# ENR153_control_board.net
KiCad netlist of a schematic drawn in EAGLE
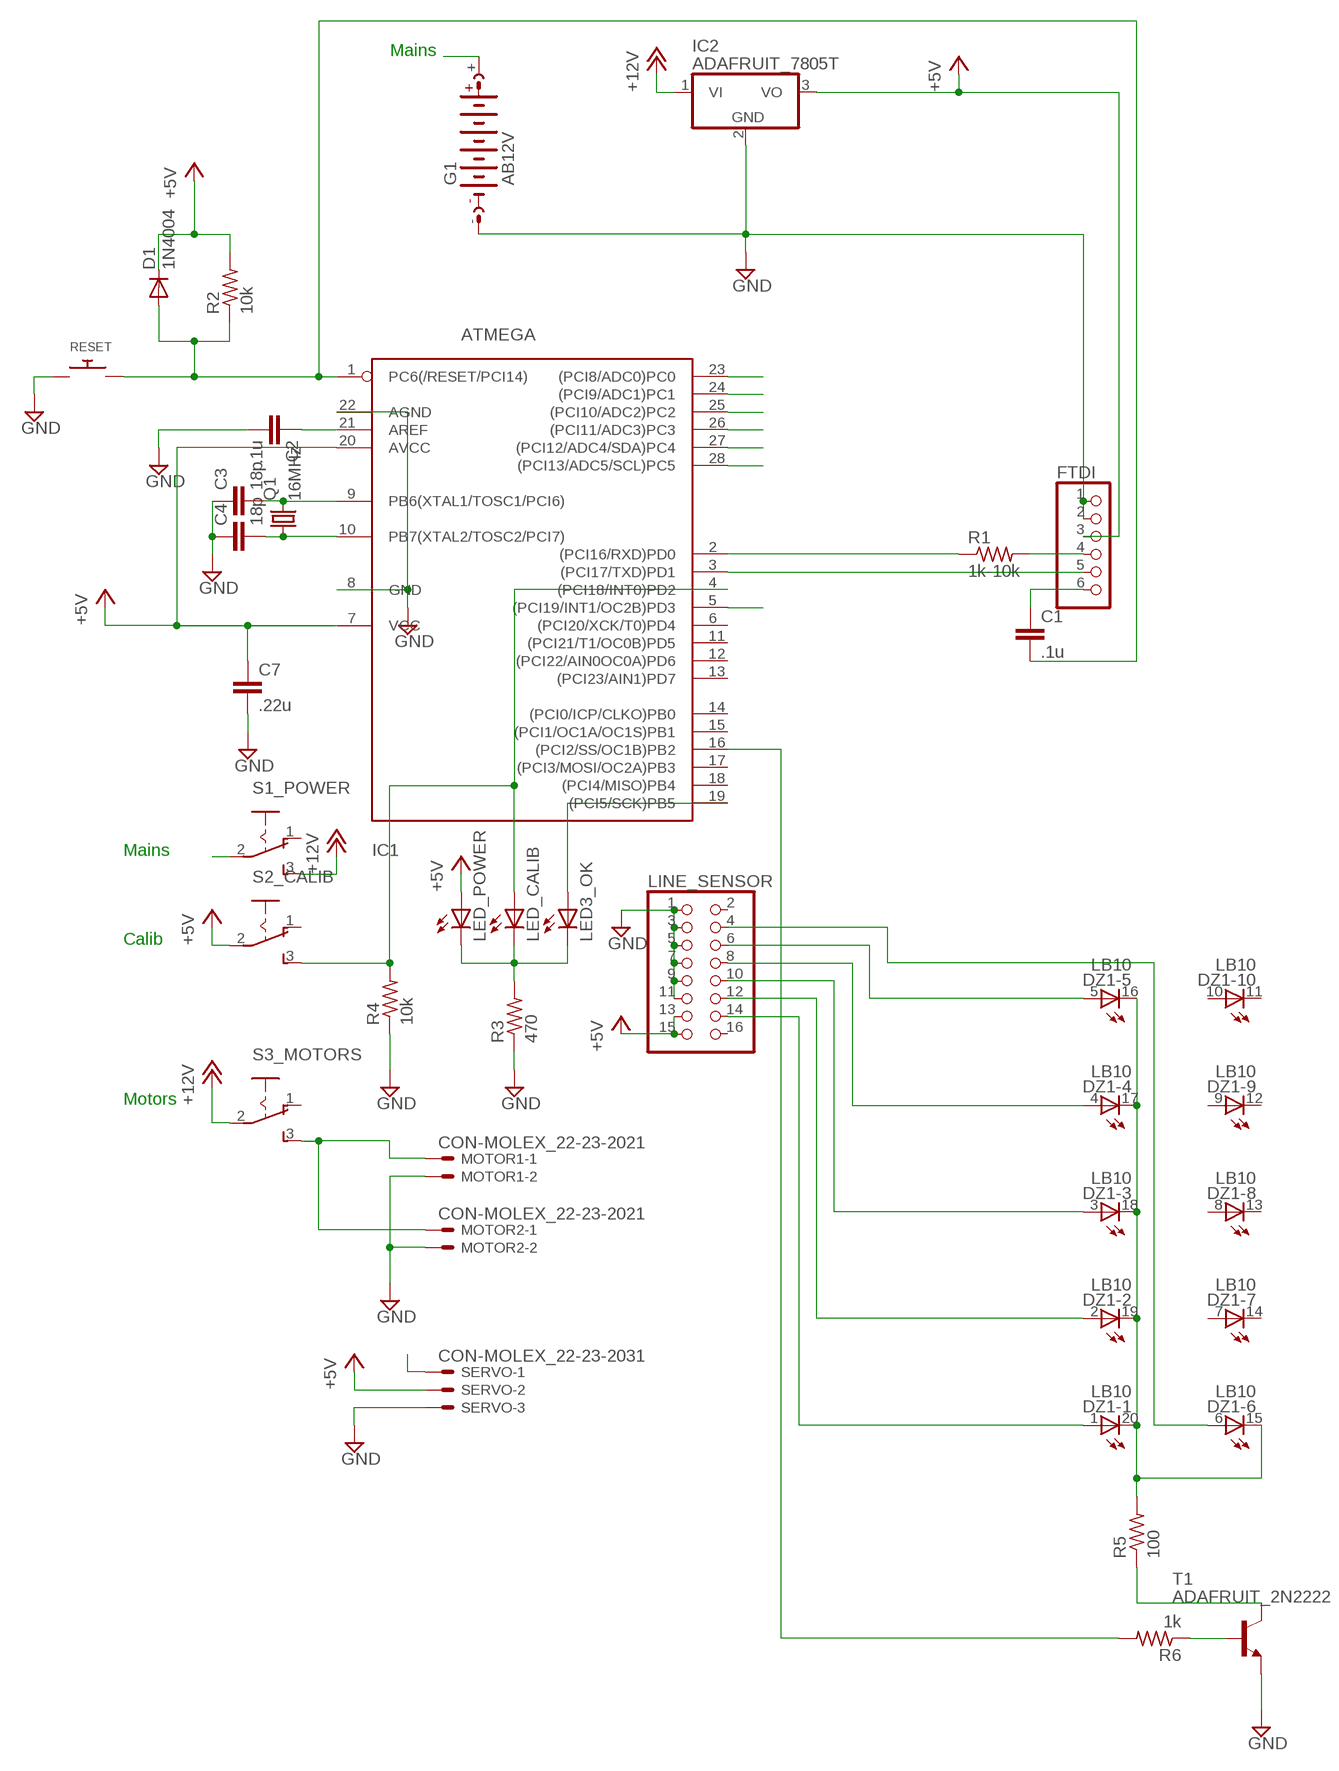
[diagram p0: schematic, sheet 1]

(export (version "E")
  (design (tool "Eeschema 10.0.6"))
  (components
    (comp (ref "C1")
      (value ".1u")
      (footprint "eagle-import:CAPACITOR-WIMA_C5B3")
      (libsource (lib "eagle-import") (part "CAPACITOR-WIMA_C5/3"))
    )
    (comp (ref "C2")
      (value ".1u")
      (footprint "eagle-import:CAPACITOR-WIMA_C5B3")
      (libsource (lib "eagle-import") (part "CAPACITOR-WIMA_C5/3"))
    )
    (comp (ref "C3")
      (value "18p")
      (footprint "eagle-import:CAPACITOR-WIMA_C5B3")
      (libsource (lib "eagle-import") (part "CAPACITOR-WIMA_C5/3"))
    )
    (comp (ref "C4")
      (value "18p")
      (footprint "eagle-import:CAPACITOR-WIMA_C5B3")
      (libsource (lib "eagle-import") (part "CAPACITOR-WIMA_C5/3"))
    )
    (comp (ref "C7")
      (value ".22u")
      (footprint "eagle-import:CAPACITOR-WIMA_C5B3")
      (libsource (lib "eagle-import") (part "CAPACITOR-WIMA_C5/3"))
    )
    (comp (ref "D1")
      (value "1N4004")
      (footprint "eagle-import:DIODE_DO35-7")
      (libsource (lib "eagle-import") (part "DIODE_1N4148DO35-7"))
    )
    (comp (ref "DZ1")
      (value "LB10")
      (footprint "eagle-import:LB10")
      (libsource (lib "eagle-import") (part "LB10"))
    )
    (comp (ref "FTDI")
      (value "PINHD-1X6")
      (footprint "eagle-import:1X06")
      (libsource (lib "eagle-import") (part "PINHD-1X6"))
    )
    (comp (ref "G1")
      (value "AB12V")
      (footprint "eagle-import:BATTERY_AB9V")
      (libsource (lib "eagle-import") (part "BATTERY_AB9V"))
    )
    (comp (ref "IC1")
      (value "ATMEGA")
      (footprint "eagle-import:DIL28-3")
      (libsource (lib "eagle-import") (part "ATMEGA168PV-10"))
    )
    (comp (ref "IC2")
      (value "ADAFRUIT_7805T")
      (footprint "eagle-import:ADAFRUIT_TO220H")
      (libsource (lib "eagle-import") (part "ADAFRUIT_78T05"))
    )
    (comp (ref "LED3_OK")
      (value "ADAFRUIT_LEDSQR2X5")
      (footprint "eagle-import:ADAFRUIT_LED2X5")
      (libsource (lib "eagle-import") (part "ADAFRUIT_LEDSQR2X5"))
    )
    (comp (ref "LED_CALIB")
      (value "ADAFRUIT_LEDSQR2X5")
      (footprint "eagle-import:ADAFRUIT_LED2X5")
      (libsource (lib "eagle-import") (part "ADAFRUIT_LEDSQR2X5"))
    )
    (comp (ref "LED_POWER")
      (value "ADAFRUIT_LEDSQR2X5")
      (footprint "eagle-import:ADAFRUIT_LED2X5")
      (libsource (lib "eagle-import") (part "ADAFRUIT_LEDSQR2X5"))
    )
    (comp (ref "LINE_SENSOR")
      (value "PINHEAD_PINHD-2X8")
      (footprint "eagle-import:PINHEAD_2X08")
      (libsource (lib "eagle-import") (part "PINHEAD_PINHD-2X8"))
    )
    (comp (ref "MOTOR1")
      (value "CON-MOLEX_22-23-2021")
      (footprint "eagle-import:CON-MOLEX_22-23-2021")
      (fields (field (name "MF") "MOLEX") (field (name "MPN") "22-23-2021"))
      (libsource (lib "eagle-import") (part "CON-MOLEX_22-23-2021"))
    )
    (comp (ref "MOTOR2")
      (value "CON-MOLEX_22-23-2021")
      (footprint "eagle-import:CON-MOLEX_22-23-2021")
      (fields (field (name "MF") "MOLEX") (field (name "MPN") "22-23-2021"))
      (libsource (lib "eagle-import") (part "CON-MOLEX_22-23-2021"))
    )
    (comp (ref "Q1")
      (value "16MHz")
      (footprint "eagle-import:ADAFRUIT_HC49_S")
      (libsource (lib "eagle-import") (part "ADAFRUIT_CRYSTALHC49S"))
    )
    (comp (ref "R1")
      (value "1k-10k")
      (footprint "eagle-import:ADAFRUIT_0207_7")
      (libsource (lib "eagle-import") (part "ADAFRUIT_R-US_0207/7"))
    )
    (comp (ref "R2")
      (value "10k")
      (footprint "eagle-import:ADAFRUIT_0207_7")
      (libsource (lib "eagle-import") (part "ADAFRUIT_R-US_0207/7"))
    )
    (comp (ref "R3")
      (value "470")
      (footprint "eagle-import:ADAFRUIT_0207_7")
      (libsource (lib "eagle-import") (part "ADAFRUIT_R-US_0207/7"))
    )
    (comp (ref "R4")
      (value "10k")
      (footprint "eagle-import:ADAFRUIT_0207_7")
      (libsource (lib "eagle-import") (part "ADAFRUIT_R-US_0207/7"))
    )
    (comp (ref "R5")
      (value "100")
      (footprint "eagle-import:ADAFRUIT_0207_7")
      (libsource (lib "eagle-import") (part "ADAFRUIT_R-US_0207/7"))
    )
    (comp (ref "R6")
      (value "1k")
      (footprint "eagle-import:ADAFRUIT_0207_7")
      (libsource (lib "eagle-import") (part "ADAFRUIT_R-US_0207/7"))
    )
    (comp (ref "RESET")
      (value "ADAFRUIT_SWITCH_PUSHBUTTONEVQ-PE")
      (footprint "eagle-import:ADAFRUIT_TACT_PANA-EVQ")
      (libsource (lib "eagle-import") (part "ADAFRUIT_SWITCH_PUSHBUTTONEVQ-PE"))
    )
    (comp (ref "S1_POWER")
      (value "SWITCH_255SB")
      (footprint "eagle-import:SWITCH_255SB")
      (libsource (lib "eagle-import") (part "SWITCH_255SB"))
    )
    (comp (ref "S2_CALIB")
      (value "SWITCH_255SB")
      (footprint "eagle-import:SWITCH_255SB")
      (libsource (lib "eagle-import") (part "SWITCH_255SB"))
    )
    (comp (ref "S3_MOTORS")
      (value "SWITCH_255SB")
      (footprint "eagle-import:SWITCH_255SB")
      (libsource (lib "eagle-import") (part "SWITCH_255SB"))
    )
    (comp (ref "SERVO")
      (value "CON-MOLEX_22-23-2031")
      (footprint "eagle-import:CON-MOLEX_22-23-2031")
      (fields (field (name "MF") "MOLEX") (field (name "MPN") "22-23-2031"))
      (libsource (lib "eagle-import") (part "CON-MOLEX_22-23-2031"))
    )
    (comp (ref "T1")
      (value "ADAFRUIT_2N2222")
      (footprint "eagle-import:ADAFRUIT_TO92-EBC-OVAL")
      (libsource (lib "eagle-import") (part "ADAFRUIT_2N2222"))
    )
  )
  (nets
    (net (code "1") (name "+5V") (class "Default")
      (node (ref "C7") (pin "1") (pinfunction "1_1") (pintype "passive"))
      (node (ref "D1") (pin "C") (pinfunction "C_C") (pintype "passive"))
      (node (ref "FTDI") (pin "3") (pinfunction "3_3") (pintype "passive"))
      (node (ref "IC1") (pin "20") (pinfunction "AVCC_20") (pintype "bidirectional"))
      (node (ref "IC1") (pin "7") (pinfunction "VCC_7") (pintype "bidirectional"))
      (node (ref "IC2") (pin "3") (pinfunction "VO_3") (pintype "passive"))
      (node (ref "LED_POWER") (pin "A") (pinfunction "A_A") (pintype "passive"))
      (node (ref "LINE_SENSOR") (pin "13") (pinfunction "13_13") (pintype "passive"))
      (node (ref "LINE_SENSOR") (pin "15") (pinfunction "15_15") (pintype "passive"))
      (node (ref "R2") (pin "2") (pinfunction "2_2") (pintype "passive"))
      (node (ref "S2_CALIB") (pin "2") (pinfunction "P_2") (pintype "passive"))
      (node (ref "SERVO") (pin "2") (pinfunction "S_2") (pintype "passive"))
    )
    (net (code "2") (name "+12V") (class "Default")
      (node (ref "IC2") (pin "1") (pinfunction "VI_1") (pintype "input"))
      (node (ref "S1_POWER") (pin "3") (pinfunction "S_3") (pintype "passive"))
      (node (ref "S3_MOTORS") (pin "2") (pinfunction "P_2") (pintype "passive"))
    )
    (net (code "3") (name "/A0") (class "Default")
      (node (ref "DZ1") (pin "6") (pinfunction "A_6") (pintype "passive"))
      (node (ref "IC1") (pin "23") (pinfunction "(PCI8/ADC0)PC0_23") (pintype "bidirectional"))
      (node (ref "LINE_SENSOR") (pin "4") (pinfunction "4_4") (pintype "passive"))
    )
    (net (code "4") (name "/A1") (class "Default")
      (node (ref "DZ1") (pin "5") (pinfunction "A_5") (pintype "passive"))
      (node (ref "IC1") (pin "24") (pinfunction "(PCI9/ADC1)PC1_24") (pintype "bidirectional"))
      (node (ref "LINE_SENSOR") (pin "6") (pinfunction "6_6") (pintype "passive"))
    )
    (net (code "5") (name "/A2") (class "Default")
      (node (ref "DZ1") (pin "4") (pinfunction "A_4") (pintype "passive"))
      (node (ref "IC1") (pin "25") (pinfunction "(PCI10/ADC2)PC2_25") (pintype "bidirectional"))
      (node (ref "LINE_SENSOR") (pin "8") (pinfunction "8_8") (pintype "passive"))
    )
    (net (code "6") (name "/A3") (class "Default")
      (node (ref "DZ1") (pin "3") (pinfunction "A_3") (pintype "passive"))
      (node (ref "IC1") (pin "26") (pinfunction "(PCI11/ADC3)PC3_26") (pintype "bidirectional"))
      (node (ref "LINE_SENSOR") (pin "10") (pinfunction "10_10") (pintype "passive"))
    )
    (net (code "7") (name "/A4") (class "Default")
      (node (ref "DZ1") (pin "2") (pinfunction "A_2") (pintype "passive"))
      (node (ref "IC1") (pin "27") (pinfunction "(PCI12/ADC4/SDA)PC4_27") (pintype "bidirectional"))
      (node (ref "LINE_SENSOR") (pin "12") (pinfunction "12_12") (pintype "passive"))
    )
    (net (code "8") (name "/A5") (class "Default")
      (node (ref "DZ1") (pin "1") (pinfunction "A_1") (pintype "passive"))
      (node (ref "IC1") (pin "28") (pinfunction "(PCI13/ADC5/SCL)PC5_28") (pintype "bidirectional"))
      (node (ref "LINE_SENSOR") (pin "14") (pinfunction "14_14") (pintype "passive"))
    )
    (net (code "9") (name "/MAINS") (class "Default")
      (node (ref "G1") (pin "+") (pinfunction "+_+") (pintype "passive"))
      (node (ref "S1_POWER") (pin "2") (pinfunction "P_2") (pintype "passive"))
    )
    (net (code "10") (name "/SERVO") (class "Default")
      (node (ref "IC1") (pin "5") (pinfunction "(PCI19/INT1/OC2B)PD3_5") (pintype "bidirectional"))
      (node (ref "SERVO") (pin "1") (pinfunction "S_1") (pintype "passive"))
    )
    (net (code "11") (name "GND") (class "Default")
      (node (ref "C2") (pin "2") (pinfunction "2_2") (pintype "passive"))
      (node (ref "C3") (pin "1") (pinfunction "1_1") (pintype "passive"))
      (node (ref "C4") (pin "1") (pinfunction "1_1") (pintype "passive"))
      (node (ref "C7") (pin "2") (pinfunction "2_2") (pintype "passive"))
      (node (ref "FTDI") (pin "1") (pinfunction "1_1") (pintype "passive"))
      (node (ref "FTDI") (pin "2") (pinfunction "2_2") (pintype "passive"))
      (node (ref "G1") (pin "-") (pinfunction "-_-") (pintype "passive"))
      (node (ref "IC1") (pin "22") (pinfunction "AGND_22") (pintype "bidirectional"))
      (node (ref "IC1") (pin "8") (pinfunction "GND_8") (pintype "bidirectional"))
      (node (ref "IC2") (pin "2") (pinfunction "GND_2") (pintype "passive"))
      (node (ref "LINE_SENSOR") (pin "1") (pinfunction "1_1") (pintype "passive"))
      (node (ref "LINE_SENSOR") (pin "11") (pinfunction "11_11") (pintype "passive"))
      (node (ref "LINE_SENSOR") (pin "3") (pinfunction "3_3") (pintype "passive"))
      (node (ref "LINE_SENSOR") (pin "5") (pinfunction "5_5") (pintype "passive"))
      (node (ref "LINE_SENSOR") (pin "7") (pinfunction "7_7") (pintype "passive"))
      (node (ref "LINE_SENSOR") (pin "9") (pinfunction "9_9") (pintype "passive"))
      (node (ref "MOTOR1") (pin "2") (pinfunction "S_2") (pintype "passive"))
      (node (ref "MOTOR2") (pin "2") (pinfunction "S_2") (pintype "passive"))
      (node (ref "R3") (pin "1") (pinfunction "1_1") (pintype "passive"))
      (node (ref "R4") (pin "1") (pinfunction "1_1") (pintype "passive"))
      (node (ref "RESET") (pin "P$1") (pinfunction "P$1_P$1") (pintype "passive"))
      (node (ref "SERVO") (pin "3") (pinfunction "S_3") (pintype "passive"))
      (node (ref "T1") (pin "E") (pinfunction "E_E") (pintype "passive"))
    )
    (net (code "12") (name "Net-(C1-Pad1)") (class "Default")
      (node (ref "C1") (pin "1") (pinfunction "1_1") (pintype "passive"))
      (node (ref "FTDI") (pin "6") (pinfunction "6_6") (pintype "passive"))
    )
    (net (code "13") (name "Net-(DZ1A-C)") (class "Default")
      (node (ref "DZ1") (pin "15") (pinfunction "C_15") (pintype "passive"))
      (node (ref "DZ1") (pin "16") (pinfunction "C_16") (pintype "passive"))
      (node (ref "DZ1") (pin "17") (pinfunction "C_17") (pintype "passive"))
      (node (ref "DZ1") (pin "18") (pinfunction "C_18") (pintype "passive"))
      (node (ref "DZ1") (pin "19") (pinfunction "C_19") (pintype "passive"))
      (node (ref "DZ1") (pin "20") (pinfunction "C_20") (pintype "passive"))
      (node (ref "R5") (pin "2") (pinfunction "2_2") (pintype "passive"))
    )
    (net (code "14") (name "Net-(FTDI-Pad4)") (class "Default")
      (node (ref "FTDI") (pin "4") (pinfunction "4_4") (pintype "passive"))
      (node (ref "R1") (pin "2") (pinfunction "2_2") (pintype "passive"))
    )
    (net (code "15") (name "Net-(IC1-(PCI2{slash}SS{slash}OC1B)PB2)") (class "Default")
      (node (ref "IC1") (pin "16") (pinfunction "(PCI2/SS/OC1B)PB2_16") (pintype "bidirectional"))
      (node (ref "R6") (pin "2") (pinfunction "2_2") (pintype "passive"))
    )
    (net (code "16") (name "Net-(IC1-(PCI5{slash}SCK)PB5)") (class "Default")
      (node (ref "IC1") (pin "19") (pinfunction "(PCI5/SCK)PB5_19") (pintype "bidirectional"))
      (node (ref "LED3_OK") (pin "A") (pinfunction "A_A") (pintype "passive"))
    )
    (net (code "17") (name "Net-(IC1-(PCI16{slash}RXD)PD0)") (class "Default")
      (node (ref "IC1") (pin "2") (pinfunction "(PCI16/RXD)PD0_2") (pintype "bidirectional"))
      (node (ref "R1") (pin "1") (pinfunction "1_1") (pintype "passive"))
    )
    (net (code "18") (name "Net-(IC1-(PCI17{slash}TXD)PD1)") (class "Default")
      (node (ref "FTDI") (pin "5") (pinfunction "5_5") (pintype "passive"))
      (node (ref "IC1") (pin "3") (pinfunction "(PCI17/TXD)PD1_3") (pintype "bidirectional"))
    )
    (net (code "19") (name "Net-(IC1-(PCI18{slash}INT0)PD2)") (class "Default")
      (node (ref "IC1") (pin "4") (pinfunction "(PCI18/INT0)PD2_4") (pintype "bidirectional"))
      (node (ref "LED_CALIB") (pin "A") (pinfunction "A_A") (pintype "passive"))
      (node (ref "R4") (pin "2") (pinfunction "2_2") (pintype "passive"))
      (node (ref "S2_CALIB") (pin "3") (pinfunction "S_3") (pintype "passive"))
    )
    (net (code "20") (name "Net-(IC1-AREF)") (class "Default")
      (node (ref "C2") (pin "1") (pinfunction "1_1") (pintype "passive"))
      (node (ref "IC1") (pin "21") (pinfunction "AREF_21") (pintype "bidirectional"))
    )
    (net (code "21") (name "Net-(IC1-PB6(XTAL1{slash}TOSC1{slash}PCI6))") (class "Default")
      (node (ref "C3") (pin "2") (pinfunction "2_2") (pintype "passive"))
      (node (ref "IC1") (pin "9") (pinfunction "PB6(XTAL1/TOSC1/PCI6)_9") (pintype "bidirectional"))
      (node (ref "Q1") (pin "2") (pinfunction "2_2") (pintype "passive"))
    )
    (net (code "22") (name "Net-(IC1-PB7(XTAL2{slash}TOSC2{slash}PCI7))") (class "Default")
      (node (ref "C4") (pin "2") (pinfunction "2_2") (pintype "passive"))
      (node (ref "IC1") (pin "10") (pinfunction "PB7(XTAL2/TOSC2/PCI7)_10") (pintype "bidirectional"))
      (node (ref "Q1") (pin "1") (pinfunction "1_1") (pintype "passive"))
    )
    (net (code "23") (name "Net-(IC1-PC6({slash}RESET{slash}PCI14))") (class "Default")
      (node (ref "C1") (pin "2") (pinfunction "2_2") (pintype "passive"))
      (node (ref "D1") (pin "A") (pinfunction "A_A") (pintype "passive"))
      (node (ref "IC1") (pin "1") (pinfunction "PC6(/RESET/PCI14)_1") (pintype "bidirectional"))
      (node (ref "R2") (pin "1") (pinfunction "1_1") (pintype "passive"))
      (node (ref "RESET") (pin "P$2") (pinfunction "P$2_P$2") (pintype "passive"))
    )
    (net (code "24") (name "Net-(LED3_OK-C)") (class "Default")
      (node (ref "LED3_OK") (pin "K") (pinfunction "C_K") (pintype "passive"))
      (node (ref "LED_CALIB") (pin "K") (pinfunction "C_K") (pintype "passive"))
      (node (ref "LED_POWER") (pin "K") (pinfunction "C_K") (pintype "passive"))
      (node (ref "R3") (pin "2") (pinfunction "2_2") (pintype "passive"))
    )
    (net (code "25") (name "Net-(MOTOR1A-S)") (class "Default")
      (node (ref "MOTOR1") (pin "1") (pinfunction "S_1") (pintype "passive"))
      (node (ref "MOTOR2") (pin "1") (pinfunction "S_1") (pintype "passive"))
      (node (ref "S3_MOTORS") (pin "3") (pinfunction "S_3") (pintype "passive"))
    )
    (net (code "26") (name "Net-(R5-Pad1)") (class "Default")
      (node (ref "R5") (pin "1") (pinfunction "1_1") (pintype "passive"))
      (node (ref "T1") (pin "C") (pinfunction "C_C") (pintype "passive"))
    )
    (net (code "27") (name "Net-(R6-Pad1)") (class "Default")
      (node (ref "R6") (pin "1") (pinfunction "1_1") (pintype "passive"))
      (node (ref "T1") (pin "B") (pinfunction "B_B") (pintype "passive"))
    )
    (net (code "28") (name "unconnected-(DZ1B-A-Pad10)") (class "Default")
      (node (ref "DZ1") (pin "10") (pinfunction "A_10") (pintype "passive"))
    )
    (net (code "29") (name "unconnected-(DZ1B-C-Pad11)") (class "Default")
      (node (ref "DZ1") (pin "11") (pinfunction "C_11") (pintype "passive"))
    )
    (net (code "30") (name "unconnected-(DZ1H-A-Pad7)") (class "Default")
      (node (ref "DZ1") (pin "7") (pinfunction "A_7") (pintype "passive"))
    )
    (net (code "31") (name "unconnected-(DZ1H-C-Pad14)") (class "Default")
      (node (ref "DZ1") (pin "14") (pinfunction "C_14") (pintype "passive"))
    )
    (net (code "32") (name "unconnected-(DZ1I-A-Pad8)") (class "Default")
      (node (ref "DZ1") (pin "8") (pinfunction "A_8") (pintype "passive"))
    )
    (net (code "33") (name "unconnected-(DZ1I-C-Pad13)") (class "Default")
      (node (ref "DZ1") (pin "13") (pinfunction "C_13") (pintype "passive"))
    )
    (net (code "34") (name "unconnected-(DZ1J-A-Pad9)") (class "Default")
      (node (ref "DZ1") (pin "9") (pinfunction "A_9") (pintype "passive"))
    )
    (net (code "35") (name "unconnected-(DZ1J-C-Pad12)") (class "Default")
      (node (ref "DZ1") (pin "12") (pinfunction "C_12") (pintype "passive"))
    )
    (net (code "36") (name "unconnected-(IC1-(PCI0{slash}ICP{slash}CLKO)PB0-Pad14)") (class "Default")
      (node (ref "IC1") (pin "14") (pinfunction "(PCI0/ICP/CLKO)PB0_14") (pintype "bidirectional"))
    )
    (net (code "37") (name "unconnected-(IC1-(PCI1{slash}OC1A{slash}OC1S)PB1-Pad15)") (class "Default")
      (node (ref "IC1") (pin "15") (pinfunction "(PCI1/OC1A/OC1S)PB1_15") (pintype "bidirectional"))
    )
    (net (code "38") (name "unconnected-(IC1-(PCI3{slash}MOSI{slash}OC2A)PB3-Pad17)") (class "Default")
      (node (ref "IC1") (pin "17") (pinfunction "(PCI3/MOSI/OC2A)PB3_17") (pintype "bidirectional"))
    )
    (net (code "39") (name "unconnected-(IC1-(PCI4{slash}MISO)PB4-Pad18)") (class "Default")
      (node (ref "IC1") (pin "18") (pinfunction "(PCI4/MISO)PB4_18") (pintype "bidirectional"))
    )
    (net (code "40") (name "unconnected-(IC1-(PCI20{slash}XCK{slash}T0)PD4-Pad6)") (class "Default")
      (node (ref "IC1") (pin "6") (pinfunction "(PCI20/XCK/T0)PD4_6") (pintype "bidirectional"))
    )
    (net (code "41") (name "unconnected-(IC1-(PCI21{slash}T1{slash}OC0B)PD5-Pad11)") (class "Default")
      (node (ref "IC1") (pin "11") (pinfunction "(PCI21/T1/OC0B)PD5_11") (pintype "bidirectional"))
    )
    (net (code "42") (name "unconnected-(IC1-(PCI22{slash}AIN0OC0A)PD6-Pad12)") (class "Default")
      (node (ref "IC1") (pin "12") (pinfunction "(PCI22/AIN0OC0A)PD6_12") (pintype "bidirectional"))
    )
    (net (code "43") (name "unconnected-(IC1-(PCI23{slash}AIN1)PD7-Pad13)") (class "Default")
      (node (ref "IC1") (pin "13") (pinfunction "(PCI23/AIN1)PD7_13") (pintype "bidirectional"))
    )
    (net (code "44") (name "unconnected-(LINE_SENSOR-Pad2)") (class "Default")
      (node (ref "LINE_SENSOR") (pin "2") (pinfunction "2_2") (pintype "passive"))
    )
    (net (code "45") (name "unconnected-(LINE_SENSOR-Pad16)") (class "Default")
      (node (ref "LINE_SENSOR") (pin "16") (pinfunction "16_16") (pintype "passive"))
    )
    (net (code "46") (name "unconnected-(S1_POWER-O-Pad1)") (class "Default")
      (node (ref "S1_POWER") (pin "1") (pinfunction "O_1") (pintype "passive"))
    )
    (net (code "47") (name "unconnected-(S2_CALIB-O-Pad1)") (class "Default")
      (node (ref "S2_CALIB") (pin "1") (pinfunction "O_1") (pintype "passive"))
    )
    (net (code "48") (name "unconnected-(S3_MOTORS-O-Pad1)") (class "Default")
      (node (ref "S3_MOTORS") (pin "1") (pinfunction "O_1") (pintype "passive"))
    )
  )
)
